# MPU-Peripherals.net
KiCad netlist of a schematic drawn in Altium Designer
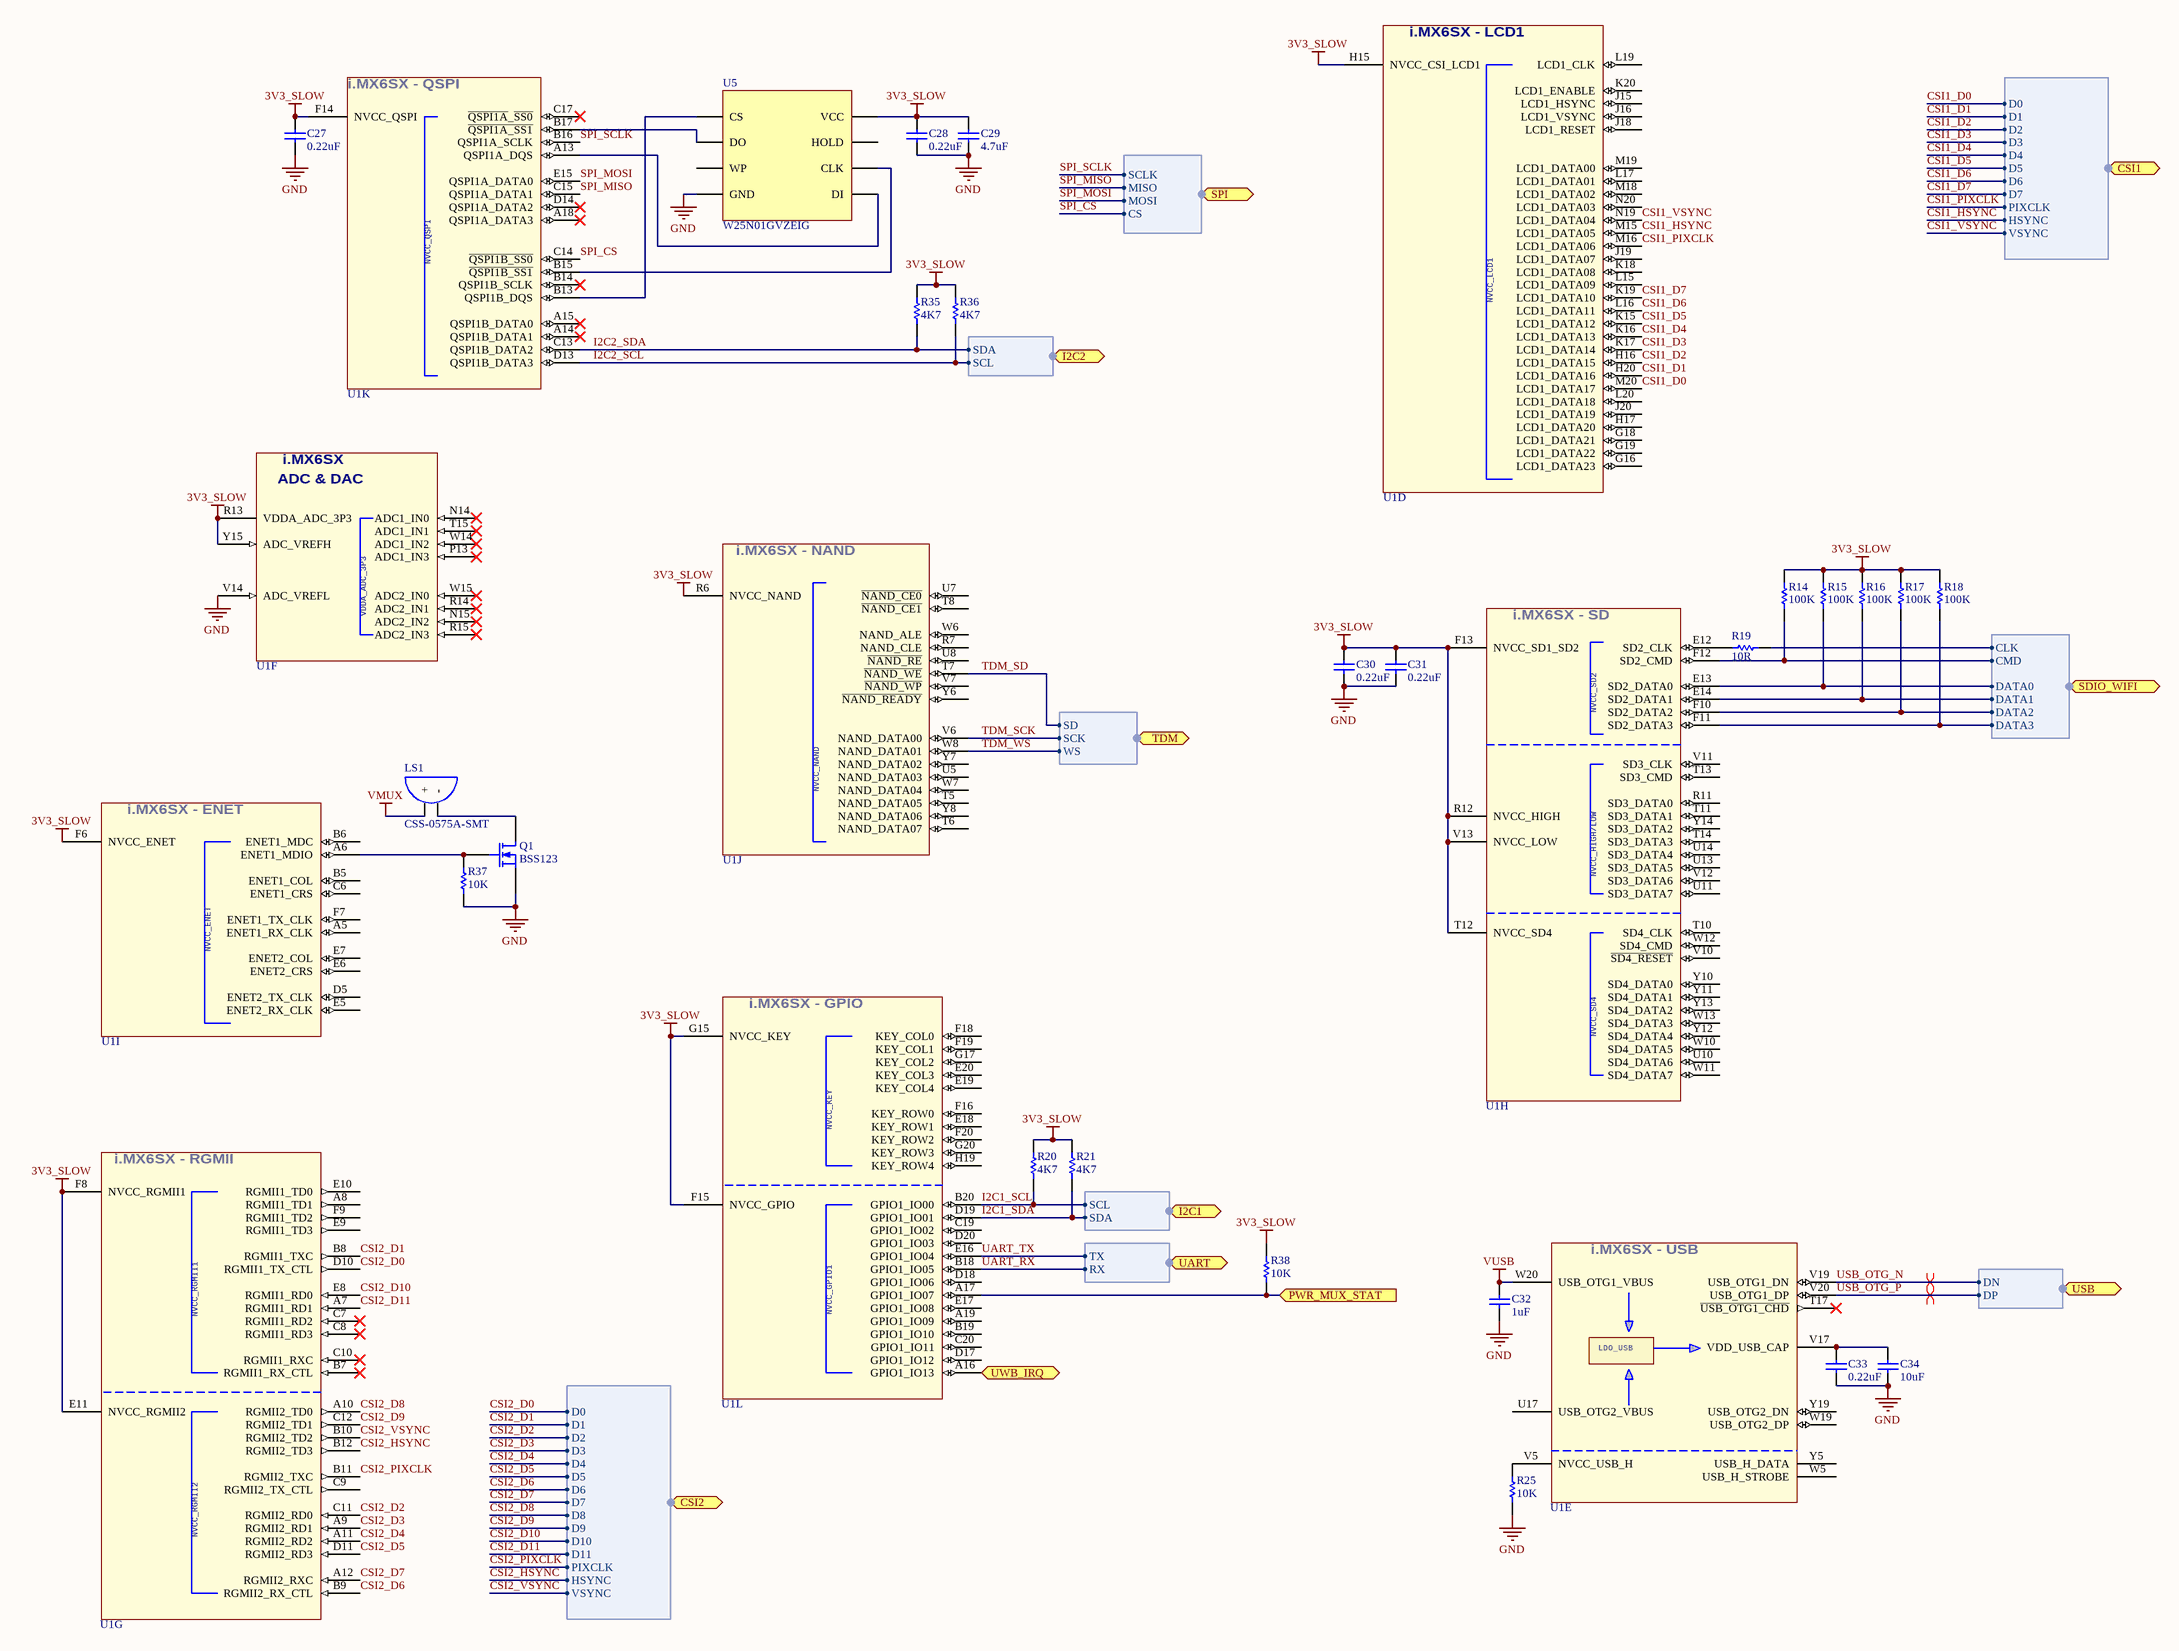
[diagram p0: MPU-Peripherals.SchDoc]

(export (version "E")
  (design (tool "Eeschema 10.0.6"))
  (components
    (comp (ref "C27")
      (value "0.22uF")
      (footprint "C0402[1005X55]")
      (description "0.22uF 6.3V 10% 0402 (1005 Metric)")
      (fields (field (name "PARTNUMBER") "JMK105BJ224KV-F") (field (name "MANUFACTURER") "Taiyo Yuden"))
      (libsource (lib "Capacitors") (part "CAP_0.22uF_6.3V_0402_10%"))
    )
    (comp (ref "C28")
      (value "0.22uF")
      (footprint "C0402[1005X55]")
      (description "0.22uF 6.3V 10% 0402 (1005 Metric)")
      (fields (field (name "PARTNUMBER") "JMK105BJ224KV-F") (field (name "MANUFACTURER") "Taiyo Yuden"))
      (libsource (lib "Capacitors") (part "CAP_0.22uF_6.3V_0402_10%"))
    )
    (comp (ref "C29")
      (value "4.7uF")
      (footprint "C0402[1005X55]")
      (description "4.7uF 6.3V 20% 0402 (1005 Metric)")
      (fields (field (name "PARTNUMBER") "GRM155R60J475ME47D") (field (name "MANUFACTURER") "Murata"))
      (libsource (lib "Capacitors") (part "CAP_4.7uF_6.3V_0402_20%"))
    )
    (comp (ref "C30")
      (value "0.22uF")
      (footprint "C0402[1005X55]")
      (description "0.22uF 6.3V 10% 0402 (1005 Metric)")
      (fields (field (name "PARTNUMBER") "JMK105BJ224KV-F") (field (name "MANUFACTURER") "Taiyo Yuden"))
      (libsource (lib "Capacitors") (part "CAP_0.22uF_6.3V_0402_10%"))
    )
    (comp (ref "C31")
      (value "0.22uF")
      (footprint "C0402[1005X55]")
      (description "0.22uF 6.3V 10% 0402 (1005 Metric)")
      (fields (field (name "PARTNUMBER") "JMK105BJ224KV-F") (field (name "MANUFACTURER") "Taiyo Yuden"))
      (libsource (lib "Capacitors") (part "CAP_0.22uF_6.3V_0402_10%"))
    )
    (comp (ref "C32")
      (value "1uF")
      (footprint "C0402[1005X55]")
      (description "1uF 16V 10% 0402 (1005 Metric)")
      (fields (field (name "PARTNUMBER") "GRM155R61C105KE01D") (field (name "MANUFACTURER") "Murata"))
      (libsource (lib "Capacitors") (part "CAP_1uF_16V_0402_10%"))
    )
    (comp (ref "C33")
      (value "0.22uF")
      (footprint "C0402[1005X55]")
      (description "0.22uF 6.3V 10% 0402 (1005 Metric)")
      (fields (field (name "PARTNUMBER") "JMK105BJ224KV-F") (field (name "MANUFACTURER") "Taiyo Yuden"))
      (libsource (lib "Capacitors") (part "CAP_0.22uF_6.3V_0402_10%"))
    )
    (comp (ref "C34")
      (value "10uF")
      (footprint "C0402[1005X55]")
      (description "10uF 6.3V 20% 0402 (1005 Metric)")
      (fields (field (name "PARTNUMBER") "GRM155R60J106ME44D") (field (name "MANUFACTURER") "Murata"))
      (libsource (lib "Capacitors") (part "CAP_10uF_6.3V_0402_20%"))
    )
    (comp (ref "LS1")
      (value "CSS-0575A-SMT")
      (footprint "CSS-0575A-SMT")
      (description "Magnetic Buzzer Transducer")
      (fields (field (name "MANUFACTURER") "CUI, Inc."))
      (libsource (lib "Components") (part "CSS-0575A-SMT"))
    )
    (comp (ref "Q1")
      (value "BSS123")
      (footprint "SOT323-3")
      (description "N-Channel MOSFET")
      (fields (field (name "PARTNUMBER") "BSS123WQ-7-F") (field (name "MANUFACTURER") "Diodes Incorporated"))
      (libsource (lib "MOSFETs") (part "BSS123WQ-7-F"))
    )
    (comp (ref "R14")
      (value "100K")
      (footprint "R0402[1005]")
      (description "100K 0.063W 1% 0402 (1005 Metric)")
      (fields (field (name "MANUFACTURER") "KOA Speer") (field (name "PARTNUMBER") "RK73H1ETTP1003F"))
      (libsource (lib "Resistors") (part "RES_100K_0402_1%"))
    )
    (comp (ref "R15")
      (value "100K")
      (footprint "R0402[1005]")
      (description "100K 0.063W 1% 0402 (1005 Metric)")
      (fields (field (name "MANUFACTURER") "KOA Speer") (field (name "PARTNUMBER") "RK73H1ETTP1003F"))
      (libsource (lib "Resistors") (part "RES_100K_0402_1%"))
    )
    (comp (ref "R16")
      (value "100K")
      (footprint "R0402[1005]")
      (description "100K 0.063W 1% 0402 (1005 Metric)")
      (fields (field (name "MANUFACTURER") "KOA Speer") (field (name "PARTNUMBER") "RK73H1ETTP1003F"))
      (libsource (lib "Resistors") (part "RES_100K_0402_1%"))
    )
    (comp (ref "R17")
      (value "100K")
      (footprint "R0402[1005]")
      (description "100K 0.063W 1% 0402 (1005 Metric)")
      (fields (field (name "MANUFACTURER") "KOA Speer") (field (name "PARTNUMBER") "RK73H1ETTP1003F"))
      (libsource (lib "Resistors") (part "RES_100K_0402_1%"))
    )
    (comp (ref "R18")
      (value "100K")
      (footprint "R0402[1005]")
      (description "100K 0.063W 1% 0402 (1005 Metric)")
      (fields (field (name "MANUFACTURER") "KOA Speer") (field (name "PARTNUMBER") "RK73H1ETTP1003F"))
      (libsource (lib "Resistors") (part "RES_100K_0402_1%"))
    )
    (comp (ref "R19")
      (value "10R")
      (footprint "R0402[1005]")
      (description "10R 0.063W 1% 0402 (1005 Metric)")
      (fields (field (name "MANUFACTURER") "KOA Speer") (field (name "PARTNUMBER") "RK73H1ETTP10R0F"))
      (libsource (lib "Resistors") (part "RES_10R_0402_1%"))
    )
    (comp (ref "R20")
      (value "4K7")
      (footprint "R0402[1005]")
      (description "4K7 0.063W 1% 0402 (1005 Metric)")
      (fields (field (name "MANUFACTURER") "KOA Speer") (field (name "PARTNUMBER") "RK73H1ETTP4701F"))
      (libsource (lib "Resistors") (part "RES_4K7_0402_1%"))
    )
    (comp (ref "R21")
      (value "4K7")
      (footprint "R0402[1005]")
      (description "4K7 0.063W 1% 0402 (1005 Metric)")
      (fields (field (name "MANUFACTURER") "KOA Speer") (field (name "PARTNUMBER") "RK73H1ETTP4701F"))
      (libsource (lib "Resistors") (part "RES_4K7_0402_1%"))
    )
    (comp (ref "R25")
      (value "10K")
      (footprint "R0402[1005]")
      (description "10K 0.063W 1% 0402 (1005 Metric)")
      (fields (field (name "MANUFACTURER") "KOA Speer") (field (name "PARTNUMBER") "RK73H1ETTP1002F"))
      (libsource (lib "Resistors") (part "RES_10K_0402_1%"))
    )
    (comp (ref "R35")
      (value "4K7")
      (footprint "R0402[1005]")
      (description "4K7 0.063W 1% 0402 (1005 Metric)")
      (fields (field (name "MANUFACTURER") "KOA Speer") (field (name "PARTNUMBER") "RK73H1ETTP4701F"))
      (libsource (lib "Resistors") (part "RES_4K7_0402_1%"))
    )
    (comp (ref "R36")
      (value "4K7")
      (footprint "R0402[1005]")
      (description "4K7 0.063W 1% 0402 (1005 Metric)")
      (fields (field (name "MANUFACTURER") "KOA Speer") (field (name "PARTNUMBER") "RK73H1ETTP4701F"))
      (libsource (lib "Resistors") (part "RES_4K7_0402_1%"))
    )
    (comp (ref "R37")
      (value "10K")
      (footprint "R0402[1005]")
      (description "10K 0.063W 1% 0402 (1005 Metric)")
      (fields (field (name "MANUFACTURER") "KOA Speer") (field (name "PARTNUMBER") "RK73H1ETTP1002F"))
      (libsource (lib "Resistors") (part "RES_10K_0402_1%"))
    )
    (comp (ref "R38")
      (value "10K")
      (footprint "R0402[1005]")
      (description "10K 0.063W 1% 0402 (1005 Metric)")
      (fields (field (name "MANUFACTURER") "KOA Speer") (field (name "PARTNUMBER") "RK73H1ETTP1002F"))
      (libsource (lib "Resistors") (part "RES_10K_0402_1%"))
    )
    (comp (ref "U1")
      (value "MCIMX6X3EVO10AB")
      (footprint "BGA-400")
      (description "IC MPU I.MX6SX 1GHZ 400MAPBGA")
      (fields (field (name "MANUFACTURER") "NXP"))
      (libsource (lib "ICs") (part "MCIMX6X3EVO10AB"))
    )
    (comp (ref "U5")
      (value "W25N01GVZEIG")
      (footprint "WSON-8 (6X8MM)")
      (fields (field (name "MANUFACTURER") "Winbond Electronics"))
      (libsource (lib "ICs") (part "W25N01GVZEIG"))
    )
  )
  (nets
    (net (code "9") (name "/CLK") (class "Default")
      (node (ref "R19") (pin "2") (pinfunction "2_2") (pintype "passive"))
    )
    (net (code "10") (name "/CMD") (class "Default")
      (node (ref "R14") (pin "1") (pinfunction "1_1") (pintype "passive"))
      (node (ref "U1") (pin "F12") (pinfunction "SD2_CMD_F12") (pintype "bidirectional"))
    )
    (net (code "11") (name "/CSI1_D0") (class "Default")
      (node (ref "U1") (pin "M20") (pinfunction "LCD1_DATA17_M20") (pintype "bidirectional"))
    )
    (net (code "12") (name "/CSI1_D1") (class "Default")
      (node (ref "U1") (pin "H20") (pinfunction "LCD1_DATA16_H20") (pintype "bidirectional"))
    )
    (net (code "13") (name "/CSI1_D2") (class "Default")
      (node (ref "U1") (pin "H16") (pinfunction "LCD1_DATA15_H16") (pintype "bidirectional"))
    )
    (net (code "14") (name "/CSI1_D3") (class "Default")
      (node (ref "U1") (pin "K17") (pinfunction "LCD1_DATA14_K17") (pintype "bidirectional"))
    )
    (net (code "15") (name "/CSI1_D4") (class "Default")
      (node (ref "U1") (pin "K16") (pinfunction "LCD1_DATA13_K16") (pintype "bidirectional"))
    )
    (net (code "16") (name "/CSI1_D5") (class "Default")
      (node (ref "U1") (pin "K15") (pinfunction "LCD1_DATA12_K15") (pintype "bidirectional"))
    )
    (net (code "17") (name "/CSI1_D6") (class "Default")
      (node (ref "U1") (pin "L16") (pinfunction "LCD1_DATA11_L16") (pintype "bidirectional"))
    )
    (net (code "18") (name "/CSI1_D7") (class "Default")
      (node (ref "U1") (pin "K19") (pinfunction "LCD1_DATA10_K19") (pintype "bidirectional"))
    )
    (net (code "19") (name "/CSI1_HSYNC") (class "Default")
      (node (ref "U1") (pin "M15") (pinfunction "LCD1_DATA05_M15") (pintype "bidirectional"))
    )
    (net (code "20") (name "/CSI1_PIXCLK") (class "Default")
      (node (ref "U1") (pin "M16") (pinfunction "LCD1_DATA06_M16") (pintype "bidirectional"))
    )
    (net (code "21") (name "/CSI1_VSYNC") (class "Default")
      (node (ref "U1") (pin "N19") (pinfunction "LCD1_DATA04_N19") (pintype "bidirectional"))
    )
    (net (code "22") (name "/CSI2_D0") (class "Default")
      (node (ref "U1") (pin "D10") (pinfunction "RGMII1_TX_CTL_D10") (pintype "output"))
    )
    (net (code "23") (name "/CSI2_D1") (class "Default")
      (node (ref "U1") (pin "B8") (pinfunction "RGMII1_TXC_B8") (pintype "output"))
    )
    (net (code "24") (name "/CSI2_D2") (class "Default")
      (node (ref "U1") (pin "C11") (pinfunction "RGMII2_RD0_C11") (pintype "input"))
    )
    (net (code "25") (name "/CSI2_D3") (class "Default")
      (node (ref "U1") (pin "A9") (pinfunction "RGMII2_RD1_A9") (pintype "input"))
    )
    (net (code "26") (name "/CSI2_D4") (class "Default")
      (node (ref "U1") (pin "A11") (pinfunction "RGMII2_RD2_A11") (pintype "input"))
    )
    (net (code "27") (name "/CSI2_D5") (class "Default")
      (node (ref "U1") (pin "D11") (pinfunction "RGMII2_RD3_D11") (pintype "input"))
    )
    (net (code "28") (name "/CSI2_D6") (class "Default")
      (node (ref "U1") (pin "B9") (pinfunction "RGMII2_RX_CTL_B9") (pintype "input"))
    )
    (net (code "29") (name "/CSI2_D7") (class "Default")
      (node (ref "U1") (pin "A12") (pinfunction "RGMII2_RXC_A12") (pintype "input"))
    )
    (net (code "30") (name "/CSI2_D8") (class "Default")
      (node (ref "U1") (pin "A10") (pinfunction "RGMII2_TD0_A10") (pintype "output"))
    )
    (net (code "31") (name "/CSI2_D9") (class "Default")
      (node (ref "U1") (pin "C12") (pinfunction "RGMII2_TD1_C12") (pintype "output"))
    )
    (net (code "32") (name "/CSI2_D10") (class "Default")
      (node (ref "U1") (pin "E8") (pinfunction "RGMII1_RD0_E8") (pintype "input"))
    )
    (net (code "33") (name "/CSI2_D11") (class "Default")
      (node (ref "U1") (pin "A7") (pinfunction "RGMII1_RD1_A7") (pintype "input"))
    )
    (net (code "34") (name "/CSI2_HSYNC") (class "Default")
      (node (ref "U1") (pin "B12") (pinfunction "RGMII2_TD3_B12") (pintype "output"))
    )
    (net (code "35") (name "/CSI2_PIXCLK") (class "Default")
      (node (ref "U1") (pin "B11") (pinfunction "RGMII2_TXC_B11") (pintype "output"))
    )
    (net (code "36") (name "/CSI2_VSYNC") (class "Default")
      (node (ref "U1") (pin "B10") (pinfunction "RGMII2_TD2_B10") (pintype "output"))
    )
    (net (code "37") (name "/DATA0") (class "Default")
      (node (ref "R15") (pin "1") (pinfunction "1_1") (pintype "passive"))
      (node (ref "U1") (pin "E13") (pinfunction "SD2_DATA0_E13") (pintype "bidirectional"))
    )
    (net (code "38") (name "/DATA1") (class "Default")
      (node (ref "R16") (pin "1") (pinfunction "1_1") (pintype "passive"))
      (node (ref "U1") (pin "E14") (pinfunction "SD2_DATA1_E14") (pintype "bidirectional"))
    )
    (net (code "39") (name "/DATA2") (class "Default")
      (node (ref "R17") (pin "1") (pinfunction "1_1") (pintype "passive"))
      (node (ref "U1") (pin "F10") (pinfunction "SD2_DATA2_F10") (pintype "bidirectional"))
    )
    (net (code "40") (name "/DATA3") (class "Default")
      (node (ref "R18") (pin "1") (pinfunction "1_1") (pintype "passive"))
      (node (ref "U1") (pin "F11") (pinfunction "SD2_DATA3_F11") (pintype "bidirectional"))
    )
    (net (code "41") (name "/I2C1_SCL") (class "Default")
      (node (ref "R20") (pin "1") (pinfunction "1_1") (pintype "passive"))
      (node (ref "U1") (pin "B20") (pinfunction "GPIO1_IO00_B20") (pintype "bidirectional"))
    )
    (net (code "42") (name "/I2C1_SDA") (class "Default")
      (node (ref "R21") (pin "1") (pinfunction "1_1") (pintype "passive"))
      (node (ref "U1") (pin "D19") (pinfunction "GPIO1_IO01_D19") (pintype "bidirectional"))
    )
    (net (code "43") (name "/I2C2_SCL") (class "Default")
      (node (ref "R36") (pin "1") (pinfunction "1_1") (pintype "passive"))
      (node (ref "U1") (pin "D13") (pinfunction "QSPI1B_DATA3_D13") (pintype "bidirectional"))
    )
    (net (code "44") (name "/I2C2_SDA") (class "Default")
      (node (ref "R35") (pin "1") (pinfunction "1_1") (pintype "passive"))
      (node (ref "U1") (pin "C13") (pinfunction "QSPI1B_DATA2_C13") (pintype "bidirectional"))
    )
    (net (code "45") (name "/PWR_MUX_STAT") (class "Default")
      (node (ref "R38") (pin "1") (pinfunction "1_1") (pintype "passive"))
      (node (ref "U1") (pin "A17") (pinfunction "GPIO1_IO07_A17") (pintype "bidirectional"))
    )
    (net (code "46") (name "/SPI_CS") (class "Default")
      (node (ref "U1") (pin "C14") (pinfunction "~{QSPI1B_SS0}_C14") (pintype "bidirectional"))
    )
    (net (code "47") (name "/SPI_MISO") (class "Default")
      (node (ref "U1") (pin "C15") (pinfunction "QSPI1A_DATA1_C15") (pintype "bidirectional"))
    )
    (net (code "48") (name "/SPI_MOSI") (class "Default")
      (node (ref "U1") (pin "E15") (pinfunction "QSPI1A_DATA0_E15") (pintype "bidirectional"))
    )
    (net (code "49") (name "/SPI_SCLK") (class "Default")
      (node (ref "U1") (pin "B16") (pinfunction "QSPI1A_SCLK_B16") (pintype "bidirectional"))
    )
    (net (code "50") (name "/TDM_SCK") (class "Default")
      (node (ref "U1") (pin "V6") (pinfunction "NAND_DATA00_V6") (pintype "bidirectional"))
    )
    (net (code "51") (name "/TDM_SD") (class "Default")
      (node (ref "U1") (pin "T7") (pinfunction "~{NAND_WE}_T7") (pintype "bidirectional"))
    )
    (net (code "52") (name "/TDM_WS") (class "Default")
      (node (ref "U1") (pin "W8") (pinfunction "NAND_DATA01_W8") (pintype "bidirectional"))
    )
    (net (code "53") (name "/UART_RX") (class "Default")
      (node (ref "U1") (pin "B18") (pinfunction "GPIO1_IO05_B18") (pintype "bidirectional"))
    )
    (net (code "54") (name "/UART_TX") (class "Default")
      (node (ref "U1") (pin "E16") (pinfunction "GPIO1_IO04_E16") (pintype "bidirectional"))
    )
    (net (code "55") (name "/USB_OTG_N") (class "Default")
      (node (ref "U1") (pin "V19") (pinfunction "USB_OTG1_DN_V19") (pintype "bidirectional"))
    )
    (net (code "56") (name "/USB_OTG_P") (class "Default")
      (node (ref "U1") (pin "V20") (pinfunction "USB_OTG1_DP_V20") (pintype "bidirectional"))
    )
    (net (code "57") (name "/UWB_IRQ") (class "Default")
      (node (ref "U1") (pin "A16") (pinfunction "GPIO1_IO13_A16") (pintype "bidirectional"))
    )
    (net (code "66") (name "3V3_SLOW") (class "Default")
      (node (ref "C27") (pin "2") (pinfunction "2_2") (pintype "passive"))
      (node (ref "C28") (pin "2") (pinfunction "2_2") (pintype "passive"))
      (node (ref "C29") (pin "2") (pinfunction "2_2") (pintype "passive"))
      (node (ref "C30") (pin "2") (pinfunction "2_2") (pintype "passive"))
      (node (ref "C31") (pin "2") (pinfunction "2_2") (pintype "passive"))
      (node (ref "R14") (pin "2") (pinfunction "2_2") (pintype "passive"))
      (node (ref "R15") (pin "2") (pinfunction "2_2") (pintype "passive"))
      (node (ref "R16") (pin "2") (pinfunction "2_2") (pintype "passive"))
      (node (ref "R17") (pin "2") (pinfunction "2_2") (pintype "passive"))
      (node (ref "R18") (pin "2") (pinfunction "2_2") (pintype "passive"))
      (node (ref "R20") (pin "2") (pinfunction "2_2") (pintype "passive"))
      (node (ref "R21") (pin "2") (pinfunction "2_2") (pintype "passive"))
      (node (ref "R35") (pin "2") (pinfunction "2_2") (pintype "passive"))
      (node (ref "R36") (pin "2") (pinfunction "2_2") (pintype "passive"))
      (node (ref "R38") (pin "2") (pinfunction "2_2") (pintype "passive"))
      (node (ref "U1") (pin "E11") (pinfunction "NVCC_RGMII2_E11") (pintype "power_in"))
      (node (ref "U1") (pin "F13") (pinfunction "NVCC_SD1_SD2_F13") (pintype "power_in"))
      (node (ref "U1") (pin "F14") (pinfunction "NVCC_QSPI_F14") (pintype "power_in"))
      (node (ref "U1") (pin "F15") (pinfunction "NVCC_GPIO_F15") (pintype "power_in"))
      (node (ref "U1") (pin "F6") (pinfunction "NVCC_ENET_F6") (pintype "power_in"))
      (node (ref "U1") (pin "F8") (pinfunction "NVCC_RGMII1_F8") (pintype "power_in"))
      (node (ref "U1") (pin "G15") (pinfunction "NVCC_KEY_G15") (pintype "power_in"))
      (node (ref "U1") (pin "H15") (pinfunction "NVCC_CSI_LCD1_H15") (pintype "power_in"))
      (node (ref "U1") (pin "R12") (pinfunction "NVCC_HIGH_R12") (pintype "power_in"))
      (node (ref "U1") (pin "R13") (pinfunction "VDDA_ADC_3P3_R13") (pintype "power_in"))
      (node (ref "U1") (pin "R6") (pinfunction "NVCC_NAND_R6") (pintype "power_in"))
      (node (ref "U1") (pin "T12") (pinfunction "NVCC_SD4_T12") (pintype "power_in"))
      (node (ref "U1") (pin "V13") (pinfunction "NVCC_LOW_V13") (pintype "power_in"))
      (node (ref "U1") (pin "Y15") (pinfunction "ADC_VREFH_Y15") (pintype "input"))
      (node (ref "U5") (pin "8") (pinfunction "VCC_8") (pintype "passive"))
    )
    (net (code "67") (name "GND") (class "Default")
      (node (ref "C27") (pin "1") (pinfunction "1_1") (pintype "passive"))
      (node (ref "C28") (pin "1") (pinfunction "1_1") (pintype "passive"))
      (node (ref "C29") (pin "1") (pinfunction "1_1") (pintype "passive"))
      (node (ref "C30") (pin "1") (pinfunction "1_1") (pintype "passive"))
      (node (ref "C31") (pin "1") (pinfunction "1_1") (pintype "passive"))
      (node (ref "C32") (pin "1") (pinfunction "1_1") (pintype "passive"))
      (node (ref "C33") (pin "1") (pinfunction "1_1") (pintype "passive"))
      (node (ref "C34") (pin "1") (pinfunction "1_1") (pintype "passive"))
      (node (ref "Q1") (pin "2") (pinfunction "S_2") (pintype "passive"))
      (node (ref "R25") (pin "1") (pinfunction "1_1") (pintype "passive"))
      (node (ref "R37") (pin "1") (pinfunction "1_1") (pintype "passive"))
      (node (ref "U1") (pin "V14") (pinfunction "ADC_VREFL_V14") (pintype "input"))
      (node (ref "U5") (pin "4") (pinfunction "GND_4") (pintype "passive"))
    )
    (net (code "68") (name "Net-(LS1--)") (class "Default")
      (node (ref "LS1") (pin "2") (pinfunction "-_2") (pintype "passive"))
      (node (ref "Q1") (pin "3") (pinfunction "D_3") (pintype "passive"))
    )
    (net (code "69") (name "Net-(Q1-G)") (class "Default")
      (node (ref "Q1") (pin "1") (pinfunction "G_1") (pintype "passive"))
      (node (ref "R37") (pin "2") (pinfunction "2_2") (pintype "passive"))
      (node (ref "U1") (pin "A6") (pinfunction "ENET1_MDIO_A6") (pintype "bidirectional"))
    )
    (net (code "70") (name "Net-(U1E-NVCC_USB_H)") (class "Default")
      (node (ref "R25") (pin "2") (pinfunction "2_2") (pintype "passive"))
      (node (ref "U1") (pin "V5") (pinfunction "NVCC_USB_H_V5") (pintype "power_in"))
    )
    (net (code "71") (name "Net-(U1E-VDD_USB_CAP)") (class "Default")
      (node (ref "C33") (pin "2") (pinfunction "2_2") (pintype "passive"))
      (node (ref "C34") (pin "2") (pinfunction "2_2") (pintype "passive"))
      (node (ref "U1") (pin "V17") (pinfunction "VDD_USB_CAP_V17") (pintype "power_in"))
    )
    (net (code "72") (name "Net-(U1H-SD2_CLK)") (class "Default")
      (node (ref "R19") (pin "1") (pinfunction "1_1") (pintype "passive"))
      (node (ref "U1") (pin "E12") (pinfunction "SD2_CLK_E12") (pintype "bidirectional"))
    )
    (net (code "73") (name "Net-(U1K-QSPI1A_DQS)") (class "Default")
      (node (ref "U1") (pin "A13") (pinfunction "QSPI1A_DQS_A13") (pintype "bidirectional"))
      (node (ref "U5") (pin "5") (pinfunction "DI_5") (pintype "power_in"))
    )
    (net (code "74") (name "Net-(U1K-QSPI1B_DQS)") (class "Default")
      (node (ref "U1") (pin "B13") (pinfunction "QSPI1B_DQS_B13") (pintype "bidirectional"))
      (node (ref "U5") (pin "1") (pinfunction "CS_1") (pintype "passive"))
    )
    (net (code "75") (name "Net-(U1K-~{QSPI1A_SS1})") (class "Default")
      (node (ref "U1") (pin "B17") (pinfunction "~{QSPI1A_SS1}_B17") (pintype "bidirectional"))
      (node (ref "U5") (pin "2") (pinfunction "DO_2") (pintype "passive"))
    )
    (net (code "76") (name "Net-(U1K-~{QSPI1B_SS1})") (class "Default")
      (node (ref "U1") (pin "B15") (pinfunction "~{QSPI1B_SS1}_B15") (pintype "bidirectional"))
      (node (ref "U5") (pin "6") (pinfunction "CLK_6") (pintype "passive"))
    )
    (net (code "77") (name "VMUX") (class "Default")
      (node (ref "LS1") (pin "1") (pinfunction "+_1") (pintype "passive"))
    )
    (net (code "78") (name "VUSB") (class "Default")
      (node (ref "C32") (pin "2") (pinfunction "2_2") (pintype "passive"))
      (node (ref "U1") (pin "W20") (pinfunction "USB_OTG1_VBUS_W20") (pintype "power_in"))
    )
    (net (code "79") (name "unconnected-(U1D-LCD1_CLK-PadL19)") (class "Default")
      (node (ref "U1") (pin "L19") (pinfunction "LCD1_CLK_L19") (pintype "bidirectional"))
    )
    (net (code "80") (name "unconnected-(U1D-LCD1_DATA00-PadM19)") (class "Default")
      (node (ref "U1") (pin "M19") (pinfunction "LCD1_DATA00_M19") (pintype "bidirectional"))
    )
    (net (code "81") (name "unconnected-(U1D-LCD1_DATA01-PadL17)") (class "Default")
      (node (ref "U1") (pin "L17") (pinfunction "LCD1_DATA01_L17") (pintype "bidirectional"))
    )
    (net (code "82") (name "unconnected-(U1D-LCD1_DATA02-PadM18)") (class "Default")
      (node (ref "U1") (pin "M18") (pinfunction "LCD1_DATA02_M18") (pintype "bidirectional"))
    )
    (net (code "83") (name "unconnected-(U1D-LCD1_DATA03-PadN20)") (class "Default")
      (node (ref "U1") (pin "N20") (pinfunction "LCD1_DATA03_N20") (pintype "bidirectional"))
    )
    (net (code "84") (name "unconnected-(U1D-LCD1_DATA07-PadJ19)") (class "Default")
      (node (ref "U1") (pin "J19") (pinfunction "LCD1_DATA07_J19") (pintype "bidirectional"))
    )
    (net (code "85") (name "unconnected-(U1D-LCD1_DATA08-PadK18)") (class "Default")
      (node (ref "U1") (pin "K18") (pinfunction "LCD1_DATA08_K18") (pintype "bidirectional"))
    )
    (net (code "86") (name "unconnected-(U1D-LCD1_DATA09-PadL15)") (class "Default")
      (node (ref "U1") (pin "L15") (pinfunction "LCD1_DATA09_L15") (pintype "bidirectional"))
    )
    (net (code "87") (name "unconnected-(U1D-LCD1_DATA18-PadL20)") (class "Default")
      (node (ref "U1") (pin "L20") (pinfunction "LCD1_DATA18_L20") (pintype "bidirectional"))
    )
    (net (code "88") (name "unconnected-(U1D-LCD1_DATA19-PadJ20)") (class "Default")
      (node (ref "U1") (pin "J20") (pinfunction "LCD1_DATA19_J20") (pintype "bidirectional"))
    )
    (net (code "89") (name "unconnected-(U1D-LCD1_DATA20-PadH17)") (class "Default")
      (node (ref "U1") (pin "H17") (pinfunction "LCD1_DATA20_H17") (pintype "bidirectional"))
    )
    (net (code "90") (name "unconnected-(U1D-LCD1_DATA21-PadG18)") (class "Default")
      (node (ref "U1") (pin "G18") (pinfunction "LCD1_DATA21_G18") (pintype "bidirectional"))
    )
    (net (code "91") (name "unconnected-(U1D-LCD1_DATA22-PadG19)") (class "Default")
      (node (ref "U1") (pin "G19") (pinfunction "LCD1_DATA22_G19") (pintype "bidirectional"))
    )
    (net (code "92") (name "unconnected-(U1D-LCD1_DATA23-PadG16)") (class "Default")
      (node (ref "U1") (pin "G16") (pinfunction "LCD1_DATA23_G16") (pintype "bidirectional"))
    )
    (net (code "93") (name "unconnected-(U1D-LCD1_ENABLE-PadK20)") (class "Default")
      (node (ref "U1") (pin "K20") (pinfunction "LCD1_ENABLE_K20") (pintype "bidirectional"))
    )
    (net (code "94") (name "unconnected-(U1D-LCD1_HSYNC-PadJ15)") (class "Default")
      (node (ref "U1") (pin "J15") (pinfunction "LCD1_HSYNC_J15") (pintype "bidirectional"))
    )
    (net (code "95") (name "unconnected-(U1D-LCD1_RESET-PadJ18)") (class "Default")
      (node (ref "U1") (pin "J18") (pinfunction "LCD1_RESET_J18") (pintype "bidirectional"))
    )
    (net (code "96") (name "unconnected-(U1D-LCD1_VSYNC-PadJ16)") (class "Default")
      (node (ref "U1") (pin "J16") (pinfunction "LCD1_VSYNC_J16") (pintype "bidirectional"))
    )
    (net (code "97") (name "unconnected-(U1E-USB_H_DATA-PadY5)") (class "Default")
      (node (ref "U1") (pin "Y5") (pinfunction "USB_H_DATA_Y5") (pintype "passive"))
    )
    (net (code "98") (name "unconnected-(U1E-USB_H_STROBE-PadW5)") (class "Default")
      (node (ref "U1") (pin "W5") (pinfunction "USB_H_STROBE_W5") (pintype "passive"))
    )
    (net (code "99") (name "unconnected-(U1E-USB_OTG2_DN-PadY19)") (class "Default")
      (node (ref "U1") (pin "Y19") (pinfunction "USB_OTG2_DN_Y19") (pintype "bidirectional"))
    )
    (net (code "100") (name "unconnected-(U1E-USB_OTG2_DP-PadW19)") (class "Default")
      (node (ref "U1") (pin "W19") (pinfunction "USB_OTG2_DP_W19") (pintype "bidirectional"))
    )
    (net (code "101") (name "unconnected-(U1E-USB_OTG2_VBUS-PadU17)") (class "Default")
      (node (ref "U1") (pin "U17") (pinfunction "USB_OTG2_VBUS_U17") (pintype "power_in"))
    )
    (net (code "102") (name "unconnected-(U1E-~{USB_OTG1_CHD}-PadT17)") (class "Default")
      (node (ref "U1") (pin "T17") (pinfunction "~{USB_OTG1_CHD}_T17") (pintype "output+no_connect"))
    )
    (net (code "103") (name "unconnected-(U1F-ADC1_IN0-PadN14)") (class "Default")
      (node (ref "U1") (pin "N14") (pinfunction "ADC1_IN0_N14") (pintype "input+no_connect"))
    )
    (net (code "104") (name "unconnected-(U1F-ADC1_IN1-PadT15)") (class "Default")
      (node (ref "U1") (pin "T15") (pinfunction "ADC1_IN1_T15") (pintype "input+no_connect"))
    )
    (net (code "105") (name "unconnected-(U1F-ADC1_IN2-PadW14)") (class "Default")
      (node (ref "U1") (pin "W14") (pinfunction "ADC1_IN2_W14") (pintype "input+no_connect"))
    )
    (net (code "106") (name "unconnected-(U1F-ADC1_IN3-PadP13)") (class "Default")
      (node (ref "U1") (pin "P13") (pinfunction "ADC1_IN3_P13") (pintype "input+no_connect"))
    )
    (net (code "107") (name "unconnected-(U1F-ADC2_IN0-PadW15)") (class "Default")
      (node (ref "U1") (pin "W15") (pinfunction "ADC2_IN0_W15") (pintype "input+no_connect"))
    )
    (net (code "108") (name "unconnected-(U1F-ADC2_IN1-PadR14)") (class "Default")
      (node (ref "U1") (pin "R14") (pinfunction "ADC2_IN1_R14") (pintype "input+no_connect"))
    )
    (net (code "109") (name "unconnected-(U1F-ADC2_IN2-PadN15)") (class "Default")
      (node (ref "U1") (pin "N15") (pinfunction "ADC2_IN2_N15") (pintype "input+no_connect"))
    )
    (net (code "110") (name "unconnected-(U1F-ADC2_IN3-PadR15)") (class "Default")
      (node (ref "U1") (pin "R15") (pinfunction "ADC2_IN3_R15") (pintype "input+no_connect"))
    )
    (net (code "111") (name "unconnected-(U1G-RGMII1_RD2-PadC7)") (class "Default")
      (node (ref "U1") (pin "C7") (pinfunction "RGMII1_RD2_C7") (pintype "input+no_connect"))
    )
    (net (code "112") (name "unconnected-(U1G-RGMII1_RD3-PadC8)") (class "Default")
      (node (ref "U1") (pin "C8") (pinfunction "RGMII1_RD3_C8") (pintype "input+no_connect"))
    )
    (net (code "113") (name "unconnected-(U1G-RGMII1_RXC-PadC10)") (class "Default")
      (node (ref "U1") (pin "C10") (pinfunction "RGMII1_RXC_C10") (pintype "input+no_connect"))
    )
    (net (code "114") (name "unconnected-(U1G-RGMII1_RX_CTL-PadB7)") (class "Default")
      (node (ref "U1") (pin "B7") (pinfunction "RGMII1_RX_CTL_B7") (pintype "input+no_connect"))
    )
    (net (code "115") (name "unconnected-(U1G-RGMII1_TD0-PadE10)") (class "Default")
      (node (ref "U1") (pin "E10") (pinfunction "RGMII1_TD0_E10") (pintype "output"))
    )
    (net (code "116") (name "unconnected-(U1G-RGMII1_TD1-PadA8)") (class "Default")
      (node (ref "U1") (pin "A8") (pinfunction "RGMII1_TD1_A8") (pintype "output"))
    )
    (net (code "117") (name "unconnected-(U1G-RGMII1_TD2-PadF9)") (class "Default")
      (node (ref "U1") (pin "F9") (pinfunction "RGMII1_TD2_F9") (pintype "output"))
    )
    (net (code "118") (name "unconnected-(U1G-RGMII1_TD3-PadE9)") (class "Default")
      (node (ref "U1") (pin "E9") (pinfunction "RGMII1_TD3_E9") (pintype "output"))
    )
    (net (code "119") (name "unconnected-(U1G-RGMII2_TX_CTL-PadC9)") (class "Default")
      (node (ref "U1") (pin "C9") (pinfunction "RGMII2_TX_CTL_C9") (pintype "output"))
    )
    (net (code "120") (name "unconnected-(U1H-SD3_CLK-PadV11)") (class "Default")
      (node (ref "U1") (pin "V11") (pinfunction "SD3_CLK_V11") (pintype "bidirectional"))
    )
    (net (code "121") (name "unconnected-(U1H-SD3_CMD-PadT13)") (class "Default")
      (node (ref "U1") (pin "T13") (pinfunction "SD3_CMD_T13") (pintype "bidirectional"))
    )
    (net (code "122") (name "unconnected-(U1H-SD3_DATA0-PadR11)") (class "Default")
      (node (ref "U1") (pin "R11") (pinfunction "SD3_DATA0_R11") (pintype "bidirectional"))
    )
    (net (code "123") (name "unconnected-(U1H-SD3_DATA1-PadT11)") (class "Default")
      (node (ref "U1") (pin "T11") (pinfunction "SD3_DATA1_T11") (pintype "bidirectional"))
    )
    (net (code "124") (name "unconnected-(U1H-SD3_DATA2-PadY14)") (class "Default")
      (node (ref "U1") (pin "Y14") (pinfunction "SD3_DATA2_Y14") (pintype "bidirectional"))
    )
    (net (code "125") (name "unconnected-(U1H-SD3_DATA3-PadT14)") (class "Default")
      (node (ref "U1") (pin "T14") (pinfunction "SD3_DATA3_T14") (pintype "bidirectional"))
    )
    (net (code "126") (name "unconnected-(U1H-SD3_DATA4-PadU14)") (class "Default")
      (node (ref "U1") (pin "U14") (pinfunction "SD3_DATA4_U14") (pintype "bidirectional"))
    )
    (net (code "127") (name "unconnected-(U1H-SD3_DATA5-PadU13)") (class "Default")
      (node (ref "U1") (pin "U13") (pinfunction "SD3_DATA5_U13") (pintype "bidirectional"))
    )
    (net (code "128") (name "unconnected-(U1H-SD3_DATA6-PadV12)") (class "Default")
      (node (ref "U1") (pin "V12") (pinfunction "SD3_DATA6_V12") (pintype "bidirectional"))
    )
    (net (code "129") (name "unconnected-(U1H-SD3_DATA7-PadU11)") (class "Default")
      (node (ref "U1") (pin "U11") (pinfunction "SD3_DATA7_U11") (pintype "bidirectional"))
    )
    (net (code "130") (name "unconnected-(U1H-SD4_CLK-PadT10)") (class "Default")
      (node (ref "U1") (pin "T10") (pinfunction "SD4_CLK_T10") (pintype "bidirectional"))
    )
    (net (code "131") (name "unconnected-(U1H-SD4_CMD-PadW12)") (class "Default")
      (node (ref "U1") (pin "W12") (pinfunction "SD4_CMD_W12") (pintype "bidirectional"))
    )
    (net (code "132") (name "unconnected-(U1H-SD4_DATA0-PadY10)") (class "Default")
      (node (ref "U1") (pin "Y10") (pinfunction "SD4_DATA0_Y10") (pintype "bidirectional"))
    )
    (net (code "133") (name "unconnected-(U1H-SD4_DATA1-PadY11)") (class "Default")
      (node (ref "U1") (pin "Y11") (pinfunction "SD4_DATA1_Y11") (pintype "bidirectional"))
    )
    (net (code "134") (name "unconnected-(U1H-SD4_DATA2-PadY13)") (class "Default")
      (node (ref "U1") (pin "Y13") (pinfunction "SD4_DATA2_Y13") (pintype "bidirectional"))
    )
    (net (code "135") (name "unconnected-(U1H-SD4_DATA3-PadW13)") (class "Default")
      (node (ref "U1") (pin "W13") (pinfunction "SD4_DATA3_W13") (pintype "bidirectional"))
    )
    (net (code "136") (name "unconnected-(U1H-SD4_DATA4-PadY12)") (class "Default")
      (node (ref "U1") (pin "Y12") (pinfunction "SD4_DATA4_Y12") (pintype "bidirectional"))
    )
    (net (code "137") (name "unconnected-(U1H-SD4_DATA5-PadW10)") (class "Default")
      (node (ref "U1") (pin "W10") (pinfunction "SD4_DATA5_W10") (pintype "bidirectional"))
    )
    (net (code "138") (name "unconnected-(U1H-SD4_DATA6-PadU10)") (class "Default")
      (node (ref "U1") (pin "U10") (pinfunction "SD4_DATA6_U10") (pintype "bidirectional"))
    )
    (net (code "139") (name "unconnected-(U1H-SD4_DATA7-PadW11)") (class "Default")
      (node (ref "U1") (pin "W11") (pinfunction "SD4_DATA7_W11") (pintype "bidirectional"))
    )
    (net (code "140") (name "unconnected-(U1H-~{SD4_RESET}-PadV10)") (class "Default")
      (node (ref "U1") (pin "V10") (pinfunction "~{SD4_RESET}_V10") (pintype "bidirectional"))
    )
    (net (code "141") (name "unconnected-(U1I-ENET1_COL-PadB5)") (class "Default")
      (node (ref "U1") (pin "B5") (pinfunction "ENET1_COL_B5") (pintype "bidirectional"))
    )
    (net (code "142") (name "unconnected-(U1I-ENET1_CRS-PadC6)") (class "Default")
      (node (ref "U1") (pin "C6") (pinfunction "ENET1_CRS_C6") (pintype "bidirectional"))
    )
    (net (code "143") (name "unconnected-(U1I-ENET1_MDC-PadB6)") (class "Default")
      (node (ref "U1") (pin "B6") (pinfunction "ENET1_MDC_B6") (pintype "bidirectional"))
    )
    (net (code "144") (name "unconnected-(U1I-ENET1_RX_CLK-PadA5)") (class "Default")
      (node (ref "U1") (pin "A5") (pinfunction "ENET1_RX_CLK_A5") (pintype "bidirectional"))
    )
    (net (code "145") (name "unconnected-(U1I-ENET1_TX_CLK-PadF7)") (class "Default")
      (node (ref "U1") (pin "F7") (pinfunction "ENET1_TX_CLK_F7") (pintype "bidirectional"))
    )
    (net (code "146") (name "unconnected-(U1I-ENET2_COL-PadE7)") (class "Default")
      (node (ref "U1") (pin "E7") (pinfunction "ENET2_COL_E7") (pintype "bidirectional"))
    )
    (net (code "147") (name "unconnected-(U1I-ENET2_CRS-PadE6)") (class "Default")
      (node (ref "U1") (pin "E6") (pinfunction "ENET2_CRS_E6") (pintype "bidirectional"))
    )
    (net (code "148") (name "unconnected-(U1I-ENET2_RX_CLK-PadE5)") (class "Default")
      (node (ref "U1") (pin "E5") (pinfunction "ENET2_RX_CLK_E5") (pintype "bidirectional"))
    )
    (net (code "149") (name "unconnected-(U1I-ENET2_TX_CLK-PadD5)") (class "Default")
      (node (ref "U1") (pin "D5") (pinfunction "ENET2_TX_CLK_D5") (pintype "bidirectional"))
    )
    (net (code "150") (name "unconnected-(U1J-NAND_ALE-PadW6)") (class "Default")
      (node (ref "U1") (pin "W6") (pinfunction "NAND_ALE_W6") (pintype "bidirectional"))
    )
    (net (code "151") (name "unconnected-(U1J-NAND_CLE-PadR7)") (class "Default")
      (node (ref "U1") (pin "R7") (pinfunction "NAND_CLE_R7") (pintype "bidirectional"))
    )
    (net (code "152") (name "unconnected-(U1J-NAND_DATA02-PadY7)") (class "Default")
      (node (ref "U1") (pin "Y7") (pinfunction "NAND_DATA02_Y7") (pintype "bidirectional"))
    )
    (net (code "153") (name "unconnected-(U1J-NAND_DATA03-PadU5)") (class "Default")
      (node (ref "U1") (pin "U5") (pinfunction "NAND_DATA03_U5") (pintype "bidirectional"))
    )
    (net (code "154") (name "unconnected-(U1J-NAND_DATA04-PadW7)") (class "Default")
      (node (ref "U1") (pin "W7") (pinfunction "NAND_DATA04_W7") (pintype "bidirectional"))
    )
    (net (code "155") (name "unconnected-(U1J-NAND_DATA05-PadT5)") (class "Default")
      (node (ref "U1") (pin "T5") (pinfunction "NAND_DATA05_T5") (pintype "bidirectional"))
    )
    (net (code "156") (name "unconnected-(U1J-NAND_DATA06-PadY8)") (class "Default")
      (node (ref "U1") (pin "Y8") (pinfunction "NAND_DATA06_Y8") (pintype "bidirectional"))
    )
    (net (code "157") (name "unconnected-(U1J-NAND_DATA07-PadT6)") (class "Default")
      (node (ref "U1") (pin "T6") (pinfunction "NAND_DATA07_T6") (pintype "bidirectional"))
    )
    (net (code "158") (name "unconnected-(U1J-~{NAND_CE0}-PadU7)") (class "Default")
      (node (ref "U1") (pin "U7") (pinfunction "~{NAND_CE0}_U7") (pintype "bidirectional"))
    )
    (net (code "159") (name "unconnected-(U1J-~{NAND_CE1}-PadT8)") (class "Default")
      (node (ref "U1") (pin "T8") (pinfunction "~{NAND_CE1}_T8") (pintype "bidirectional"))
    )
    (net (code "160") (name "unconnected-(U1J-~{NAND_READY}-PadY6)") (class "Default")
      (node (ref "U1") (pin "Y6") (pinfunction "~{NAND_READY}_Y6") (pintype "bidirectional"))
    )
    (net (code "161") (name "unconnected-(U1J-~{NAND_RE}-PadU8)") (class "Default")
      (node (ref "U1") (pin "U8") (pinfunction "~{NAND_RE}_U8") (pintype "bidirectional"))
    )
    (net (code "162") (name "unconnected-(U1J-~{NAND_WP}-PadV7)") (class "Default")
      (node (ref "U1") (pin "V7") (pinfunction "~{NAND_WP}_V7") (pintype "bidirectional"))
    )
    (net (code "163") (name "unconnected-(U1K-QSPI1A_DATA2-PadD14)") (class "Default")
      (node (ref "U1") (pin "D14") (pinfunction "QSPI1A_DATA2_D14") (pintype "bidirectional+no_connect"))
    )
    (net (code "164") (name "unconnected-(U1K-QSPI1A_DATA3-PadA18)") (class "Default")
      (node (ref "U1") (pin "A18") (pinfunction "QSPI1A_DATA3_A18") (pintype "bidirectional+no_connect"))
    )
    (net (code "165") (name "unconnected-(U1K-QSPI1B_DATA0-PadA15)") (class "Default")
      (node (ref "U1") (pin "A15") (pinfunction "QSPI1B_DATA0_A15") (pintype "bidirectional+no_connect"))
    )
    (net (code "166") (name "unconnected-(U1K-QSPI1B_DATA1-PadA14)") (class "Default")
      (node (ref "U1") (pin "A14") (pinfunction "QSPI1B_DATA1_A14") (pintype "bidirectional+no_connect"))
    )
    (net (code "167") (name "unconnected-(U1K-QSPI1B_SCLK-PadB14)") (class "Default")
      (node (ref "U1") (pin "B14") (pinfunction "QSPI1B_SCLK_B14") (pintype "bidirectional+no_connect"))
    )
    (net (code "168") (name "unconnected-(U1K-~{QSPI1A}_~{SS0}-PadC17)") (class "Default")
      (node (ref "U1") (pin "C17") (pinfunction "~{QSPI1A}_~{SS0}_C17") (pintype "bidirectional+no_connect"))
    )
    (net (code "169") (name "unconnected-(U1L-GPIO1_IO02-PadC19)") (class "Default")
      (node (ref "U1") (pin "C19") (pinfunction "GPIO1_IO02_C19") (pintype "bidirectional"))
    )
    (net (code "170") (name "unconnected-(U1L-GPIO1_IO03-PadD20)") (class "Default")
      (node (ref "U1") (pin "D20") (pinfunction "GPIO1_IO03_D20") (pintype "bidirectional"))
    )
    (net (code "171") (name "unconnected-(U1L-GPIO1_IO06-PadD18)") (class "Default")
      (node (ref "U1") (pin "D18") (pinfunction "GPIO1_IO06_D18") (pintype "bidirectional"))
    )
    (net (code "172") (name "unconnected-(U1L-GPIO1_IO08-PadE17)") (class "Default")
      (node (ref "U1") (pin "E17") (pinfunction "GPIO1_IO08_E17") (pintype "bidirectional"))
    )
    (net (code "173") (name "unconnected-(U1L-GPIO1_IO09-PadA19)") (class "Default")
      (node (ref "U1") (pin "A19") (pinfunction "GPIO1_IO09_A19") (pintype "bidirectional"))
    )
    (net (code "174") (name "unconnected-(U1L-GPIO1_IO10-PadB19)") (class "Default")
      (node (ref "U1") (pin "B19") (pinfunction "GPIO1_IO10_B19") (pintype "bidirectional"))
    )
    (net (code "175") (name "unconnected-(U1L-GPIO1_IO11-PadC20)") (class "Default")
      (node (ref "U1") (pin "C20") (pinfunction "GPIO1_IO11_C20") (pintype "bidirectional"))
    )
    (net (code "176") (name "unconnected-(U1L-GPIO1_IO12-PadD17)") (class "Default")
      (node (ref "U1") (pin "D17") (pinfunction "GPIO1_IO12_D17") (pintype "bidirectional"))
    )
    (net (code "177") (name "unconnected-(U1L-KEY_COL0-PadF18)") (class "Default")
      (node (ref "U1") (pin "F18") (pinfunction "KEY_COL0_F18") (pintype "bidirectional"))
    )
    (net (code "178") (name "unconnected-(U1L-KEY_COL1-PadF19)") (class "Default")
      (node (ref "U1") (pin "F19") (pinfunction "KEY_COL1_F19") (pintype "bidirectional"))
    )
    (net (code "179") (name "unconnected-(U1L-KEY_COL2-PadG17)") (class "Default")
      (node (ref "U1") (pin "G17") (pinfunction "KEY_COL2_G17") (pintype "bidirectional"))
    )
    (net (code "180") (name "unconnected-(U1L-KEY_COL3-PadE20)") (class "Default")
      (node (ref "U1") (pin "E20") (pinfunction "KEY_COL3_E20") (pintype "bidirectional"))
    )
    (net (code "181") (name "unconnected-(U1L-KEY_COL4-PadE19)") (class "Default")
      (node (ref "U1") (pin "E19") (pinfunction "KEY_COL4_E19") (pintype "bidirectional"))
    )
    (net (code "182") (name "unconnected-(U1L-KEY_ROW0-PadF16)") (class "Default")
      (node (ref "U1") (pin "F16") (pinfunction "KEY_ROW0_F16") (pintype "bidirectional"))
    )
    (net (code "183") (name "unconnected-(U1L-KEY_ROW1-PadE18)") (class "Default")
      (node (ref "U1") (pin "E18") (pinfunction "KEY_ROW1_E18") (pintype "bidirectional"))
    )
    (net (code "184") (name "unconnected-(U1L-KEY_ROW2-PadF20)") (class "Default")
      (node (ref "U1") (pin "F20") (pinfunction "KEY_ROW2_F20") (pintype "bidirectional"))
    )
    (net (code "185") (name "unconnected-(U1L-KEY_ROW3-PadG20)") (class "Default")
      (node (ref "U1") (pin "G20") (pinfunction "KEY_ROW3_G20") (pintype "bidirectional"))
    )
    (net (code "186") (name "unconnected-(U1L-KEY_ROW4-PadH19)") (class "Default")
      (node (ref "U1") (pin "H19") (pinfunction "KEY_ROW4_H19") (pintype "bidirectional"))
    )
    (net (code "187") (name "unconnected-(U5-HOLD-Pad7)") (class "Default")
      (node (ref "U5") (pin "7") (pinfunction "HOLD_7") (pintype "passive"))
    )
    (net (code "188") (name "unconnected-(U5-WP-Pad3)") (class "Default")
      (node (ref "U5") (pin "3") (pinfunction "WP_3") (pintype "passive"))
    )
  )
)
